# LP_ECG_Power-X01.net
KiCad netlist of a schematic drawn in Altium Designer
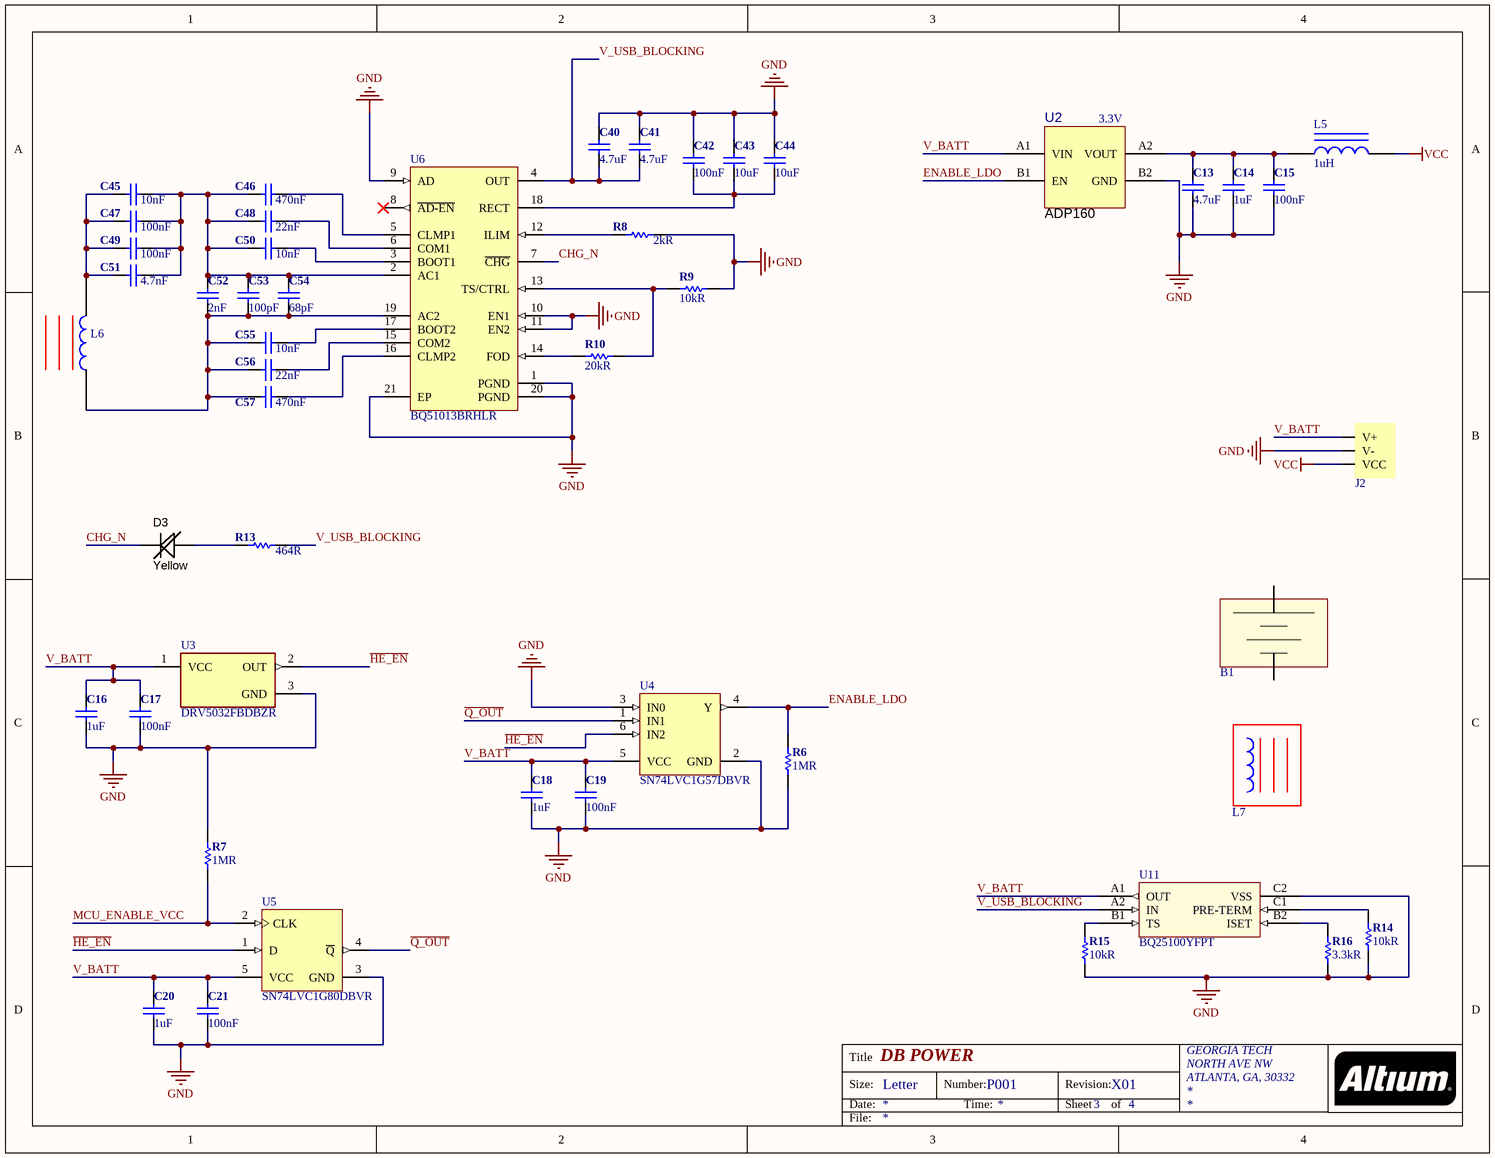
[diagram p0: LP_ECG_Power-X01.SchDoc]

(export (version "E")
  (design (tool "Eeschema 10.0.6"))
  (components
    (comp (ref "B1")
      (value "40 mAh BATTERY")
      (footprint "BATTERY")
      (description "Lithium Battery 3.7V 40mAh Rechargeable")
      (fields (field (name "MANUFACTURER") "SparkFun") (field (name "MANUFACTURER PART NUMBER") "PRT-13852"))
      (libsource (lib "LP_ECG-X01") (part "BATTERY"))
    )
    (comp (ref "C13")
      (value "4.7uF")
      (footprint "C0402")
      (fields
        (field (name "MANUFACTURER") "Murata")
        (field (name "MANUFACTURER PART NUMBER") "GRM155R60J475ME87J")
      )
      (libsource (lib "LP_ECG-X01") (part "C-0402(1005)"))
    )
    (comp (ref "C14")
      (value "1uF")
      (footprint "C0402")
      (fields
        (field (name "MANUFACTURER") "Yageo")
        (field (name "MANUFACTURER PART NUMBER") "CC0402MRX5R5BB105")
        (field (name "TOLERANCE") "20%")
      )
      (libsource (lib "LP_ECG-X01") (part "C-0402(1005)"))
    )
    (comp (ref "C15")
      (value "100nF")
      (footprint "C0402")
      (fields
        (field (name "MANUFACTURER") "Taiyo Yuden")
        (field (name "MANUFACTURER PART NUMBER") "TMK105BJ104KV-F")
        (field (name "TOLERANCE") "10%")
      )
      (libsource (lib "LP_ECG-X01") (part "C-0402(1005)"))
    )
    (comp (ref "C16")
      (value "1uF")
      (footprint "C0402")
      (fields
        (field (name "MANUFACTURER") "Yageo")
        (field (name "MANUFACTURER PART NUMBER") "CC0402MRX5R5BB105")
        (field (name "TOLERANCE") "20%")
      )
      (libsource (lib "LP_ECG-X01") (part "C-0402(1005)"))
    )
    (comp (ref "C17")
      (value "100nF")
      (footprint "C0402")
      (fields
        (field (name "MANUFACTURER") "Taiyo Yuden")
        (field (name "MANUFACTURER PART NUMBER") "TMK105BJ104KV-F")
        (field (name "TOLERANCE") "10%")
      )
      (libsource (lib "LP_ECG-X01") (part "C-0402(1005)"))
    )
    (comp (ref "C18")
      (value "1uF")
      (footprint "C0402")
      (fields
        (field (name "MANUFACTURER") "Yageo")
        (field (name "MANUFACTURER PART NUMBER") "CC0402MRX5R5BB105")
        (field (name "TOLERANCE") "20%")
      )
      (libsource (lib "LP_ECG-X01") (part "C-0402(1005)"))
    )
    (comp (ref "C19")
      (value "100nF")
      (footprint "C0402")
      (fields
        (field (name "MANUFACTURER") "Taiyo Yuden")
        (field (name "MANUFACTURER PART NUMBER") "TMK105BJ104KV-F")
        (field (name "TOLERANCE") "10%")
      )
      (libsource (lib "LP_ECG-X01") (part "C-0402(1005)"))
    )
    (comp (ref "C20")
      (value "1uF")
      (footprint "C0402")
      (fields
        (field (name "MANUFACTURER") "Yageo")
        (field (name "MANUFACTURER PART NUMBER") "CC0402MRX5R5BB105")
        (field (name "TOLERANCE") "20%")
      )
      (libsource (lib "LP_ECG-X01") (part "C-0402(1005)"))
    )
    (comp (ref "C21")
      (value "100nF")
      (footprint "C0402")
      (fields
        (field (name "MANUFACTURER") "Taiyo Yuden")
        (field (name "MANUFACTURER PART NUMBER") "TMK105BJ104KV-F")
        (field (name "TOLERANCE") "10%")
      )
      (libsource (lib "LP_ECG-X01") (part "C-0402(1005)"))
    )
    (comp (ref "C40")
      (value "4.7uF")
      (footprint "C0402")
      (fields
        (field (name "MANUFACTURER") "Murata")
        (field (name "MANUFACTURER PART NUMBER") "GRM155R60J475ME87J")
      )
      (libsource (lib "LP_ECG-X01") (part "C-0402(1005)"))
    )
    (comp (ref "C41")
      (value "4.7uF")
      (footprint "C0402")
      (fields
        (field (name "MANUFACTURER") "Murata")
        (field (name "MANUFACTURER PART NUMBER") "GRM155R60J475ME87J")
      )
      (libsource (lib "LP_ECG-X01") (part "C-0402(1005)"))
    )
    (comp (ref "C42")
      (value "100nF")
      (footprint "C0402")
      (fields
        (field (name "MANUFACTURER") "Taiyo Yuden")
        (field (name "MANUFACTURER PART NUMBER") "TMK105BJ104KV-F")
      )
      (libsource (lib "LP_ECG-X01") (part "C-0402(1005)"))
    )
    (comp (ref "C43")
      (value "10uF")
      (footprint "C0402")
      (fields
        (field (name "MANUFACTURER") "Kyocera AVX")
        (field (name "MANUFACTURER PART NUMBER") "0402ZD106MAT2A")
      )
      (libsource (lib "LP_ECG-X01") (part "C-0402(1005)"))
    )
    (comp (ref "C44")
      (value "10uF")
      (footprint "C0402")
      (fields
        (field (name "MANUFACTURER") "Kyocera AVX")
        (field (name "MANUFACTURER PART NUMBER") "0402ZD106MAT2A")
      )
      (libsource (lib "LP_ECG-X01") (part "C-0402(1005)"))
    )
    (comp (ref "C45")
      (value "10nF")
      (footprint "C0402")
      (fields
        (field (name "MANUFACTURER") "Yageo")
        (field (name "MANUFACTURER PART NUMBER") "CC0402JRX7R8BB103")
        (field (name "TOLERANCE") "5%")
      )
      (libsource (lib "LP_ECG-X01") (part "C-0402(1005)"))
    )
    (comp (ref "C46")
      (value "470nF")
      (footprint "C0402")
      (fields
        (field (name "MANUFACTURER") "Murata")
        (field (name "MANUFACTURER PART NUMBER") "GRT155R61E474ME01D")
        (field (name "TOLERANCE") "20%")
      )
      (libsource (lib "LP_ECG-X01") (part "C-0402(1005)"))
    )
    (comp (ref "C47")
      (value "100nF")
      (footprint "C0402")
      (fields
        (field (name "MANUFACTURER") "Taiyo Yuden")
        (field (name "MANUFACTURER PART NUMBER") "TMK105BJ104KV-F")
        (field (name "TOLERANCE") "10%")
      )
      (libsource (lib "LP_ECG-X01") (part "C-0402(1005)"))
    )
    (comp (ref "C48")
      (value "22nF")
      (footprint "C0402")
      (fields
        (field (name "MANUFACTURER") "Murata")
        (field (name "MANUFACTURER PART NUMBER") "GRM155R71E223KA61D")
        (field (name "TOLERANCE") "10%")
      )
      (libsource (lib "LP_ECG-X01") (part "C-0402(1005)"))
    )
    (comp (ref "C49")
      (value "100nF")
      (footprint "C0402")
      (fields
        (field (name "MANUFACTURER") "Taiyo Yuden")
        (field (name "MANUFACTURER PART NUMBER") "TMK105BJ104KV-F")
        (field (name "TOLERANCE") "10%")
      )
      (libsource (lib "LP_ECG-X01") (part "C-0402(1005)"))
    )
    (comp (ref "C50")
      (value "10nF")
      (footprint "C0402")
      (fields
        (field (name "MANUFACTURER") "KEMET")
        (field (name "MANUFACTURER PART NUMBER") "C0402C103J3RACTU")
        (field (name "TOLERANCE") "5%")
      )
      (libsource (lib "LP_ECG-X01") (part "C-0402(1005)"))
    )
    (comp (ref "C51")
      (value "4.7nF")
      (footprint "C0402")
      (fields
        (field (name "MANUFACTURER") "Yageo")
        (field (name "MANUFACTURER PART NUMBER") "CC0402JRX7R8BB472")
        (field (name "TOLERANCE") "5%")
      )
      (libsource (lib "LP_ECG-X01") (part "C-0402(1005)"))
    )
    (comp (ref "C52")
      (value "2nF")
      (footprint "C0402")
      (fields
        (field (name "MANUFACTURER") "KEMET")
        (field (name "MANUFACTURER PART NUMBER") "C0402C202J3GACTU")
        (field (name "TOLERANCE") "5%")
      )
      (libsource (lib "LP_ECG-X01") (part "C-0402(1005)"))
    )
    (comp (ref "C53")
      (value "100pF")
      (footprint "C0402")
      (fields
        (field (name "MANUFACTURER") "KEMET")
        (field (name "MANUFACTURER PART NUMBER") "CBR04C101F3GAC")
        (field (name "TOLERANCE") "1%")
      )
      (libsource (lib "LP_ECG-X01") (part "C-0402(1005)"))
    )
    (comp (ref "C54")
      (value "68pF")
      (footprint "C0402")
      (fields
        (field (name "MANUFACTURER") "KEMET")
        (field (name "MANUFACTURER PART NUMBER") "CBR04C680F3GAC")
        (field (name "TOLERANCE") "1%")
      )
      (libsource (lib "LP_ECG-X01") (part "C-0402(1005)"))
    )
    (comp (ref "C55")
      (value "10nF")
      (footprint "C0402")
      (fields
        (field (name "MANUFACTURER") "KEMET")
        (field (name "MANUFACTURER PART NUMBER") "C0402C103J3RACTU")
        (field (name "TOLERANCE") "5%")
      )
      (libsource (lib "LP_ECG-X01") (part "C-0402(1005)"))
    )
    (comp (ref "C56")
      (value "22nF")
      (footprint "C0402")
      (fields
        (field (name "MANUFACTURER") "Murata")
        (field (name "MANUFACTURER PART NUMBER") "GRM155R71E223KA61D")
        (field (name "TOLERANCE") "10%")
      )
      (libsource (lib "LP_ECG-X01") (part "C-0402(1005)"))
    )
    (comp (ref "C57")
      (value "470nF")
      (footprint "C0402")
      (fields
        (field (name "MANUFACTURER") "Murata")
        (field (name "MANUFACTURER PART NUMBER") "GRT155R61E474ME01D")
        (field (name "TOLERANCE") "20%")
      )
      (libsource (lib "LP_ECG-X01") (part "C-0402(1005)"))
    )
    (comp (ref "D3")
      (value "Yellow")
      (footprint "LED_0402")
      (description "Single Color LED, Super Bright Yellow, Water Clear, 0.8mm")
      (fields
        (field (name "MANUFACTURER") "Kingbright")
        (field (name "MANUFACTURER PART NUMBER") "APHHS1005SYCK")
      )
      (libsource (lib "LP_ECG-X01") (part "LED_0402(1005)"))
    )
    (comp (ref "J2")
      (value "SMD CONNECTOR FOR 40 mAh BATTERY")
      (footprint "battery_connector")
      (description "Lithium Battery 3.7V 40mAh Rechargeable")
      (libsource (lib "LP_ECG-X01") (part "SMD_BATTERY_CONNECTOR"))
    )
    (comp (ref "L5")
      (value "1uH")
      (footprint "L0402")
      (description "General Purpose Inductor, 1uH, 20%, 1 Element, Ferrite-Core, SMD, 0402")
      (fields
        (field (name "MANUFACTURER") "TDK")
        (field (name "MANUFACTURER PART NUMBER") "MLZ1005M1R0WT000")
      )
      (libsource (lib "LP_ECG-X01") (part "Inductor Iron"))
    )
    (comp (ref "L6")
      (value "WIRELESS CHARGING COIL, RECEIVER")
      (footprint "760308101219")
      (description "General Purpose Inductor, 11.8uH, 10%, 1 Element")
      (fields
        (field (name "MANUFACTURER") "Wurth Electronics")
        (field (name "MANUFACTURER PART NUMBER") "760308101219")
      )
      (libsource (lib "LP_ECG-X01") (part "WIRELESS_CHARGING_COIL"))
    )
    (comp (ref "L7")
      (value "WIRELESS CHARGING COIL, RECEIVER")
      (footprint "760308101219 - Physical Model")
      (description "Inductor")
      (libsource (lib "LP_ECG-X01") (part "WIRELESS_CHARGING-PHYSICAL_MODEL"))
    )
    (comp (ref "R6")
      (value "1MR")
      (footprint "R0402")
      (fields
        (field (name "MANUFACTURER") "Yageo")
        (field (name "MANUFACTURER PART NUMBER") "AC0402FR-071ML")
        (field (name "TOLERANCE") "1%")
      )
      (libsource (lib "LP_ECG-X01") (part "R-0402(1005)"))
    )
    (comp (ref "R7")
      (value "1MR")
      (footprint "R0402")
      (fields
        (field (name "MANUFACTURER") "Yageo")
        (field (name "MANUFACTURER PART NUMBER") "AC0402FR-071ML")
        (field (name "TOLERANCE") "1%")
      )
      (libsource (lib "LP_ECG-X01") (part "R-0402(1005)"))
    )
    (comp (ref "R8")
      (value "2kR")
      (footprint "R0402")
      (fields
        (field (name "MANUFACTURER") "Yageo")
        (field (name "MANUFACTURER PART NUMBER") "AC0402FR-072KL")
        (field (name "TOLERANCE") "1%")
      )
      (libsource (lib "LP_ECG-X01") (part "R-0402(1005)"))
    )
    (comp (ref "R9")
      (value "10kR")
      (footprint "R0402")
      (fields
        (field (name "MANUFACTURER") "Yageo")
        (field (name "MANUFACTURER PART NUMBER") "AC0402FR-0710KL")
        (field (name "TOLERANCE") "1%")
      )
      (libsource (lib "LP_ECG-X01") (part "R-0402(1005)"))
    )
    (comp (ref "R10")
      (value "20kR")
      (footprint "R0402")
      (fields
        (field (name "MANUFACTURER") "Yageo")
        (field (name "MANUFACTURER PART NUMBER") "AC0402FR-0720KL")
        (field (name "TOLERANCE") "1%")
      )
      (libsource (lib "LP_ECG-X01") (part "R-0402(1005)"))
    )
    (comp (ref "R13")
      (value "464R")
      (footprint "R0402")
      (fields
        (field (name "MANUFACTURER") "Yageo")
        (field (name "MANUFACTURER PART NUMBER") "RC0402FR-07464RL")
        (field (name "TOLERANCE") "1%")
      )
      (libsource (lib "LP_ECG-X01") (part "R-0402(1005)"))
    )
    (comp (ref "R14")
      (value "10kR")
      (footprint "R0402")
      (fields
        (field (name "MANUFACTURER") "Yageo")
        (field (name "MANUFACTURER PART NUMBER") "AC0402FR-0710KL")
        (field (name "TOLERANCE") "1%")
      )
      (libsource (lib "LP_ECG-X01") (part "R-0402(1005)"))
    )
    (comp (ref "R15")
      (value "10kR")
      (footprint "R0402")
      (fields
        (field (name "MANUFACTURER") "Yageo")
        (field (name "MANUFACTURER PART NUMBER") "AC0402FR-0710KL")
        (field (name "TOLERANCE") "1%")
      )
      (libsource (lib "LP_ECG-X01") (part "R-0402(1005)"))
    )
    (comp (ref "R16")
      (value "3.3kR")
      (footprint "R0402")
      (fields
        (field (name "MANUFACTURER") "Yageo")
        (field (name "MANUFACTURER PART NUMBER") "AC0402FR-073K3L")
        (field (name "TOLERANCE") "1%")
      )
      (libsource (lib "LP_ECG-X01") (part "R-0402(1005)"))
    )
    (comp (ref "U2")
      (value "ADP160")
      (footprint "ADP160")
      (description "Fixed Positive LDO Regulator, 3.3V, 0.195V Dropout, CMOS, PBGA4")
      (fields
        (field (name "MANUFACTURER") "Analog Devices")
        (field (name "MANUFACTURER PART NUMBER") "ADP160ACBZ-3.3-R7")
        (field (name "OUTPUT VOLTAGE") "3.3V")
      )
      (libsource (lib "LP_ECG-X01") (part "ADP160-3_3V"))
    )
    (comp (ref "U3")
      (value "DRV5032FBDBZR")
      (footprint "FP-DBZ0003A-MFG")
      (description "LP HALL 32FBDBZR")
      (fields (field (name "MANUFACTURER") "Texas Instruments"))
      (libsource (lib "Altium Content Vault") (part "2ac151be60cf6bda0d169f73a696793"))
    )
    (comp (ref "U4")
      (value "SN74LVC1G57DBVR")
      (footprint "DBV0006A_M")
      (description "CONFIGURABLE MULTIPLE-FUNCTION GATE, DBV0006A, LARGE T&R")
      (fields (field (name "MANUFACTURER") "Texas Instruments"))
      (libsource (lib "Altium Content Vault") (part "TI-SN74XXX1GXX-6"))
    )
    (comp (ref "U5")
      (value "SN74LVC1G80DBVR")
      (footprint "DBV0005A_N")
      (description "Single Positive-Edge-Triggered D-Type Flip-Flop, DBV0005A, LARGE T&R")
      (fields (field (name "MANUFACTURER") "Texas Instruments"))
      (libsource (lib "Altium Content Vault") (part "TI-SN74XXX1G80-5"))
    )
    (comp (ref "U6")
      (value "BQ51013BRHLR")
      (footprint "BQ51013BRHLR")
      (fields (field (name "MANUFACTURER") "Texas Instruments"))
      (libsource (lib "LP_ECG-X01") (part "TI-BQ51013B-RHL20"))
    )
    (comp (ref "U11")
      (value "BQ25100YFPT")
      (footprint "YZP0006")
      (description "Power Supply Support Circuit")
      (fields (field (name "MANUFACTURER") "Texas Instruments"))
      (libsource (lib "LP_ECG-X01") (part "BQ25100YFPT"))
    )
  )
  (nets
    (net (code "1") (name "/CHG_N") (class "Default")
      (node (ref "D3") (pin "K") (pinfunction "K_K") (pintype "passive"))
      (node (ref "U6") (pin "7") (pinfunction "~{CHG}_7") (pintype "open_collector"))
    )
    (net (code "2") (name "/ENABLE_LDO") (class "Default")
      (node (ref "R6") (pin "1") (pinfunction "1_1") (pintype "passive"))
      (node (ref "U2") (pin "B1") (pinfunction "EN_B1") (pintype "passive"))
      (node (ref "U4") (pin "4") (pinfunction "Y_4") (pintype "output"))
    )
    (net (code "3") (name "/MCU_ENABLE_VCC") (class "Default")
      (node (ref "R7") (pin "2") (pinfunction "2_2") (pintype "passive"))
      (node (ref "U5") (pin "2") (pinfunction "CLK_2") (pintype "input"))
    )
    (net (code "4") (name "/V_BATT") (class "Default")
      (node (ref "C16") (pin "1") (pinfunction "1_1") (pintype "passive"))
      (node (ref "C17") (pin "2") (pinfunction "2_2") (pintype "passive"))
      (node (ref "C18") (pin "1") (pinfunction "1_1") (pintype "passive"))
      (node (ref "C19") (pin "2") (pinfunction "2_2") (pintype "passive"))
      (node (ref "C20") (pin "1") (pinfunction "1_1") (pintype "passive"))
      (node (ref "C21") (pin "2") (pinfunction "2_2") (pintype "passive"))
      (node (ref "J2") (pin "1") (pinfunction "V+_1") (pintype "power_in"))
      (node (ref "U11") (pin "A1") (pinfunction "OUT_A1") (pintype "output"))
      (node (ref "U2") (pin "A1") (pinfunction "VIN_A1") (pintype "passive"))
      (node (ref "U3") (pin "1") (pinfunction "VCC_1") (pintype "power_in"))
      (node (ref "U4") (pin "5") (pinfunction "VCC_5") (pintype "power_in"))
      (node (ref "U5") (pin "5") (pinfunction "VCC_5") (pintype "power_in"))
    )
    (net (code "5") (name "/V_USB_BLOCKING") (class "Default")
      (node (ref "C40") (pin "2") (pinfunction "2_2") (pintype "passive"))
      (node (ref "C41") (pin "2") (pinfunction "2_2") (pintype "passive"))
      (node (ref "R13") (pin "2") (pinfunction "2_2") (pintype "passive"))
      (node (ref "U11") (pin "A2") (pinfunction "IN_A2") (pintype "input"))
      (node (ref "U6") (pin "4") (pinfunction "OUT_4") (pintype "power_in"))
    )
    (net (code "6") (name "/~{HE_EN}") (class "Default")
      (node (ref "U3") (pin "2") (pinfunction "OUT_2") (pintype "output"))
      (node (ref "U4") (pin "6") (pinfunction "IN2_6") (pintype "input"))
      (node (ref "U5") (pin "1") (pinfunction "D_1") (pintype "input"))
    )
    (net (code "7") (name "/~{Q_OUT}") (class "Default")
      (node (ref "U4") (pin "1") (pinfunction "IN1_1") (pintype "input"))
      (node (ref "U5") (pin "4") (pinfunction "~{Q}_4") (pintype "output"))
    )
    (net (code "8") (name "GND") (class "Default")
      (node (ref "C13") (pin "2") (pinfunction "2_2") (pintype "passive"))
      (node (ref "C14") (pin "2") (pinfunction "2_2") (pintype "passive"))
      (node (ref "C15") (pin "1") (pinfunction "1_1") (pintype "passive"))
      (node (ref "C16") (pin "2") (pinfunction "2_2") (pintype "passive"))
      (node (ref "C17") (pin "1") (pinfunction "1_1") (pintype "passive"))
      (node (ref "C18") (pin "2") (pinfunction "2_2") (pintype "passive"))
      (node (ref "C19") (pin "1") (pinfunction "1_1") (pintype "passive"))
      (node (ref "C20") (pin "2") (pinfunction "2_2") (pintype "passive"))
      (node (ref "C21") (pin "1") (pinfunction "1_1") (pintype "passive"))
      (node (ref "C40") (pin "1") (pinfunction "1_1") (pintype "passive"))
      (node (ref "C41") (pin "1") (pinfunction "1_1") (pintype "passive"))
      (node (ref "C42") (pin "1") (pinfunction "1_1") (pintype "passive"))
      (node (ref "C43") (pin "1") (pinfunction "1_1") (pintype "passive"))
      (node (ref "C44") (pin "1") (pinfunction "1_1") (pintype "passive"))
      (node (ref "J2") (pin "2") (pinfunction "V-_2") (pintype "power_in"))
      (node (ref "R14") (pin "1") (pinfunction "1_1") (pintype "passive"))
      (node (ref "R15") (pin "1") (pinfunction "1_1") (pintype "passive"))
      (node (ref "R16") (pin "1") (pinfunction "1_1") (pintype "passive"))
      (node (ref "R6") (pin "2") (pinfunction "2_2") (pintype "passive"))
      (node (ref "R7") (pin "1") (pinfunction "1_1") (pintype "passive"))
      (node (ref "R8") (pin "2") (pinfunction "2_2") (pintype "passive"))
      (node (ref "R9") (pin "2") (pinfunction "2_2") (pintype "passive"))
      (node (ref "U11") (pin "C2") (pinfunction "VSS_C2") (pintype "power_in"))
      (node (ref "U2") (pin "B2") (pinfunction "GND_B2") (pintype "passive"))
      (node (ref "U3") (pin "3") (pinfunction "GND_3") (pintype "power_in"))
      (node (ref "U4") (pin "2") (pinfunction "GND_2") (pintype "power_in"))
      (node (ref "U4") (pin "3") (pinfunction "IN0_3") (pintype "input"))
      (node (ref "U5") (pin "3") (pinfunction "GND_3") (pintype "power_in"))
      (node (ref "U6") (pin "1") (pinfunction "PGND_1") (pintype "power_in"))
      (node (ref "U6") (pin "10") (pinfunction "EN1_10") (pintype "input"))
      (node (ref "U6") (pin "11") (pinfunction "EN2_11") (pintype "input"))
      (node (ref "U6") (pin "20") (pinfunction "PGND_20") (pintype "power_in"))
      (node (ref "U6") (pin "21") (pinfunction "EP_21") (pintype "passive"))
      (node (ref "U6") (pin "9") (pinfunction "AD_9") (pintype "input"))
    )
    (net (code "9") (name "Net-(C45-Pad1)") (class "Default")
      (node (ref "C45") (pin "1") (pinfunction "1_1") (pintype "passive"))
      (node (ref "C47") (pin "1") (pinfunction "1_1") (pintype "passive"))
      (node (ref "C49") (pin "1") (pinfunction "1_1") (pintype "passive"))
      (node (ref "C51") (pin "1") (pinfunction "1_1") (pintype "passive"))
      (node (ref "L6") (pin "2") (pinfunction "2_2") (pintype "passive"))
    )
    (net (code "10") (name "Net-(D3-PadA)") (class "Default")
      (node (ref "D3") (pin "A") (pinfunction "A_A") (pintype "passive"))
      (node (ref "R13") (pin "1") (pinfunction "1_1") (pintype "passive"))
    )
    (net (code "11") (name "Net-(U2-VOUT)") (class "Default")
      (node (ref "C13") (pin "1") (pinfunction "1_1") (pintype "passive"))
      (node (ref "C14") (pin "1") (pinfunction "1_1") (pintype "passive"))
      (node (ref "C15") (pin "2") (pinfunction "2_2") (pintype "passive"))
      (node (ref "L5") (pin "1") (pinfunction "1_1") (pintype "passive"))
      (node (ref "U2") (pin "A2") (pinfunction "VOUT_A2") (pintype "passive"))
    )
    (net (code "12") (name "Net-(U6-AC1)") (class "Default")
      (node (ref "C45") (pin "2") (pinfunction "2_2") (pintype "passive"))
      (node (ref "C46") (pin "1") (pinfunction "1_1") (pintype "passive"))
      (node (ref "C47") (pin "2") (pinfunction "2_2") (pintype "passive"))
      (node (ref "C48") (pin "1") (pinfunction "1_1") (pintype "passive"))
      (node (ref "C49") (pin "2") (pinfunction "2_2") (pintype "passive"))
      (node (ref "C50") (pin "1") (pinfunction "1_1") (pintype "passive"))
      (node (ref "C51") (pin "2") (pinfunction "2_2") (pintype "passive"))
      (node (ref "C52") (pin "1") (pinfunction "1_1") (pintype "passive"))
      (node (ref "C53") (pin "1") (pinfunction "1_1") (pintype "passive"))
      (node (ref "C54") (pin "1") (pinfunction "1_1") (pintype "passive"))
      (node (ref "U6") (pin "2") (pinfunction "AC1_2") (pintype "power_in"))
    )
    (net (code "13") (name "Net-(U6-AC2)") (class "Default")
      (node (ref "C52") (pin "2") (pinfunction "2_2") (pintype "passive"))
      (node (ref "C53") (pin "2") (pinfunction "2_2") (pintype "passive"))
      (node (ref "C54") (pin "2") (pinfunction "2_2") (pintype "passive"))
      (node (ref "C55") (pin "1") (pinfunction "1_1") (pintype "passive"))
      (node (ref "C56") (pin "1") (pinfunction "1_1") (pintype "passive"))
      (node (ref "C57") (pin "1") (pinfunction "1_1") (pintype "passive"))
      (node (ref "L6") (pin "1") (pinfunction "1_1") (pintype "passive"))
      (node (ref "U6") (pin "19") (pinfunction "AC2_19") (pintype "power_in"))
    )
    (net (code "14") (name "Net-(U6-BOOT1)") (class "Default")
      (node (ref "C50") (pin "2") (pinfunction "2_2") (pintype "passive"))
      (node (ref "U6") (pin "3") (pinfunction "BOOT1_3") (pintype "passive"))
    )
    (net (code "15") (name "Net-(U6-BOOT2)") (class "Default")
      (node (ref "C55") (pin "2") (pinfunction "2_2") (pintype "passive"))
      (node (ref "U6") (pin "17") (pinfunction "BOOT2_17") (pintype "passive"))
    )
    (net (code "16") (name "Net-(U6-CLMP1)") (class "Default")
      (node (ref "C46") (pin "2") (pinfunction "2_2") (pintype "passive"))
      (node (ref "U6") (pin "5") (pinfunction "CLMP1_5") (pintype "open_collector"))
    )
    (net (code "17") (name "Net-(U6-CLMP2)") (class "Default")
      (node (ref "C57") (pin "2") (pinfunction "2_2") (pintype "passive"))
      (node (ref "U6") (pin "16") (pinfunction "CLMP2_16") (pintype "open_collector"))
    )
    (net (code "18") (name "Net-(U6-COM1)") (class "Default")
      (node (ref "C48") (pin "2") (pinfunction "2_2") (pintype "passive"))
      (node (ref "U6") (pin "6") (pinfunction "COM1_6") (pintype "open_collector"))
    )
    (net (code "19") (name "Net-(U6-COM2)") (class "Default")
      (node (ref "C56") (pin "2") (pinfunction "2_2") (pintype "passive"))
      (node (ref "U6") (pin "15") (pinfunction "COM2_15") (pintype "open_collector"))
    )
    (net (code "20") (name "Net-(U6-FOD)") (class "Default")
      (node (ref "R10") (pin "1") (pinfunction "1_1") (pintype "passive"))
      (node (ref "U6") (pin "14") (pinfunction "FOD_14") (pintype "input"))
    )
    (net (code "21") (name "Net-(U6-ILIM)") (class "Default")
      (node (ref "R8") (pin "1") (pinfunction "1_1") (pintype "passive"))
      (node (ref "U6") (pin "12") (pinfunction "ILIM_12") (pintype "input"))
    )
    (net (code "22") (name "Net-(U6-RECT)") (class "Default")
      (node (ref "C42") (pin "2") (pinfunction "2_2") (pintype "passive"))
      (node (ref "C43") (pin "2") (pinfunction "2_2") (pintype "passive"))
      (node (ref "C44") (pin "2") (pinfunction "2_2") (pintype "passive"))
      (node (ref "U6") (pin "18") (pinfunction "RECT_18") (pintype "passive"))
    )
    (net (code "23") (name "Net-(U6-TS{slash}CTRL)") (class "Default")
      (node (ref "R10") (pin "2") (pinfunction "2_2") (pintype "passive"))
      (node (ref "R9") (pin "1") (pinfunction "1_1") (pintype "passive"))
      (node (ref "U6") (pin "13") (pinfunction "TS/CTRL_13") (pintype "input"))
    )
    (net (code "24") (name "Net-(U11-ISET)") (class "Default")
      (node (ref "R16") (pin "2") (pinfunction "2_2") (pintype "passive"))
      (node (ref "U11") (pin "B2") (pinfunction "ISET_B2") (pintype "input"))
    )
    (net (code "25") (name "Net-(U11-PRE-TERM)") (class "Default")
      (node (ref "R14") (pin "2") (pinfunction "2_2") (pintype "passive"))
      (node (ref "U11") (pin "C1") (pinfunction "PRE-TERM_C1") (pintype "input"))
    )
    (net (code "26") (name "Net-(U11-TS)") (class "Default")
      (node (ref "R15") (pin "2") (pinfunction "2_2") (pintype "passive"))
      (node (ref "U11") (pin "B1") (pinfunction "TS_B1") (pintype "input"))
    )
    (net (code "27") (name "VCC") (class "Default")
      (node (ref "J2") (pin "3") (pinfunction "VCC_3") (pintype "power_in"))
      (node (ref "L5") (pin "2") (pinfunction "2_2") (pintype "passive"))
    )
    (net (code "28") (name "unconnected-(U6-~{AD-EN}-Pad8)") (class "Default")
      (node (ref "U6") (pin "8") (pinfunction "~{AD-EN}_8") (pintype "output+no_connect"))
    )
  )
)
